# token.net
KiCad netlist of a schematic drawn in EAGLE
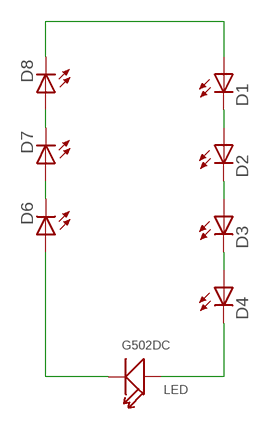
[diagram p0: schematic, sheet 1]

(export (version "E")
  (design (tool "Eeschema 10.0.6"))
  (components
    (comp (ref "D1")
      (value "LEDSQR2X5")
      (footprint "eagle-import:LED2X5")
      (libsource (lib "eagle-import") (part "LEDSQR2X5"))
    )
    (comp (ref "D2")
      (value "LEDSQR2X5")
      (footprint "eagle-import:LED2X5")
      (libsource (lib "eagle-import") (part "LEDSQR2X5"))
    )
    (comp (ref "D3")
      (value "LEDSQR2X5")
      (footprint "eagle-import:LED2X5")
      (libsource (lib "eagle-import") (part "LEDSQR2X5"))
    )
    (comp (ref "D4")
      (value "LEDSQR2X5")
      (footprint "eagle-import:LED2X5")
      (libsource (lib "eagle-import") (part "LEDSQR2X5"))
    )
    (comp (ref "D6")
      (value "LEDSQR2X5")
      (footprint "eagle-import:LED2X5")
      (libsource (lib "eagle-import") (part "LEDSQR2X5"))
    )
    (comp (ref "D7")
      (value "LEDSQR2X5")
      (footprint "eagle-import:LED2X5")
      (libsource (lib "eagle-import") (part "LEDSQR2X5"))
    )
    (comp (ref "D8")
      (value "LEDSQR2X5")
      (footprint "eagle-import:LED2X5")
      (libsource (lib "eagle-import") (part "LEDSQR2X5"))
    )
    (comp (ref "LED")
      (value "G502DC")
      (footprint "eagle-import:LED2-2.54-D5.0MM")
      (libsource (lib "eagle-import") (part "DIP-LED-GREEN-GREEN(2P-D5MM)"))
    )
  )
  (nets
    (net (code "1") (name "Net-(D1-C)") (class "Default")
      (node (ref "D1") (pin "K") (pinfunction "C_K") (pintype "passive"))
      (node (ref "D2") (pin "A") (pinfunction "A_A") (pintype "passive"))
    )
    (net (code "2") (name "Net-(D2-C)") (class "Default")
      (node (ref "D2") (pin "K") (pinfunction "C_K") (pintype "passive"))
      (node (ref "D3") (pin "A") (pinfunction "A_A") (pintype "passive"))
    )
    (net (code "3") (name "Net-(D3-C)") (class "Default")
      (node (ref "D3") (pin "K") (pinfunction "C_K") (pintype "passive"))
      (node (ref "D4") (pin "A") (pinfunction "A_A") (pintype "passive"))
    )
    (net (code "4") (name "Net-(D4-C)") (class "Default")
      (node (ref "D4") (pin "K") (pinfunction "C_K") (pintype "passive"))
      (node (ref "LED") (pin "+") (pinfunction "+_+") (pintype "passive"))
    )
    (net (code "5") (name "Net-(D6-C)") (class "Default")
      (node (ref "D6") (pin "K") (pinfunction "C_K") (pintype "passive"))
      (node (ref "D7") (pin "A") (pinfunction "A_A") (pintype "passive"))
    )
    (net (code "6") (name "Net-(D6-PadA)") (class "Default")
      (node (ref "D6") (pin "A") (pinfunction "A_A") (pintype "passive"))
      (node (ref "LED") (pin "-") (pinfunction "-_-") (pintype "passive"))
    )
    (net (code "7") (name "Net-(D7-C)") (class "Default")
      (node (ref "D7") (pin "K") (pinfunction "C_K") (pintype "passive"))
      (node (ref "D8") (pin "A") (pinfunction "A_A") (pintype "passive"))
    )
    (net (code "8") (name "Net-(D8-C)") (class "Default")
      (node (ref "D1") (pin "A") (pinfunction "A_A") (pintype "passive"))
      (node (ref "D8") (pin "K") (pinfunction "C_K") (pintype "passive"))
    )
  )
)
